# Analog_Input.net
KiCad netlist of a schematic drawn in Altium Designer
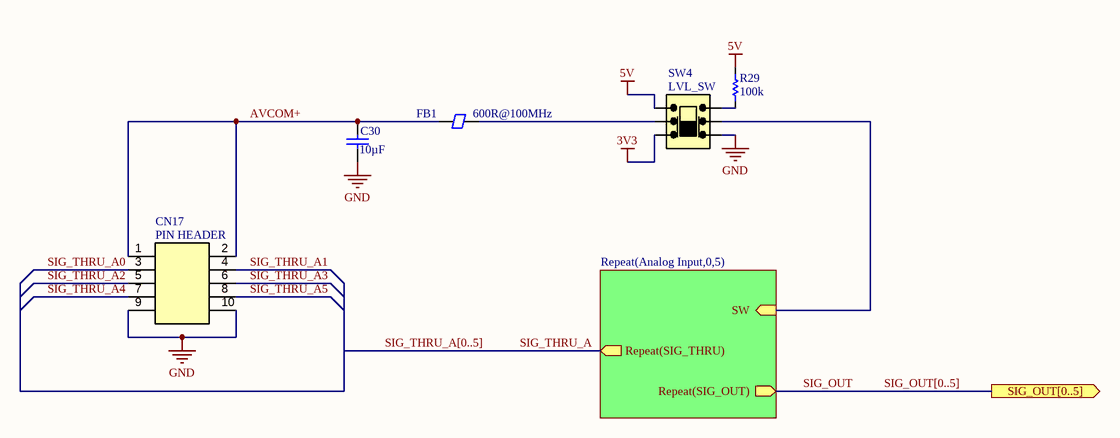
[diagram p0: Analog Input.SchDoc]

(export (version "E")
  (design (tool "Eeschema 10.0.6"))
  (components
    (comp (ref "C30")
      (value "10µF")
      (footprint "CAP_CHIP_0603")
      (fields
        (field (name "PARTNUMBER") "GRM188R6YA106MA73D")
        (field (name "TOLERANCE") "20%")
        (field (name "Comment") "C0603-10uF-35V")
      )
      (libsource (lib "Sainsbury Wellcome Centre") (part "Cap"))
    )
    (comp (ref "CN17")
      (value "PIN HEADER")
      (footprint "PIN_2.54_2X5P")
      (fields (field (name "PARTNUMBER") "PZ254V-12-10P"))
      (libsource (lib "Sainsbury Wellcome Centre") (part "Header_2X5P"))
    )
    (comp (ref "FB1")
      (value "600R@100MHz")
      (footprint "FB_CHIP_0603")
      (description "Ferrite Chip, 1 Function(s), 0.2A, 2 Pin(s)")
      (fields (field (name "PARTNUMBER") "GZ1608D601TF") (field (name "Comment") "FB0603-600R-0.2A"))
      (libsource (lib "Sainsbury Wellcome Centre") (part "Bead"))
    )
    (comp (ref "R29")
      (value "100k")
      (footprint "RES_CHIP_0603")
      (description "100mW Thick Film Resistors 75V ±100ppm/℃ ±1% 0603 Chip Resistor")
      (fields (field (name "PARTNUMBER") "0603WAF1003T5E") (field (name "TOLERANCE") "1%"))
      (libsource (lib "Sainsbury Wellcome Centre") (part "Res"))
    )
    (comp (ref "SW4")
      (value "LVL_SW")
      (footprint "SW_SLIDE_OS202013MT8")
      (description "Switch Slide ON ON DPDT Top Slide 0.3A 30VDC 10000Cycles PC Pins Thru-Hole Bulk")
      (fields (field (name "PARTNUMBER") "OS202013MT8QN1"))
      (libsource (lib "Sainsbury Wellcome Centre") (part "SLIDE_DPDT"))
    )
  )
  (nets
    (net (code "7") (name "/AVCOM+") (class "Default")
      (node (ref "C30") (pin "2") (pinfunction "2_2") (pintype "passive"))
      (node (ref "CN17") (pin "1") (pinfunction "1_1") (pintype "passive"))
      (node (ref "CN17") (pin "2") (pinfunction "2_2") (pintype "passive"))
      (node (ref "FB1") (pin "2") (pinfunction "2_2") (pintype "passive"))
    )
    (net (code "11") (name "/SIG_THRU_A0") (class "Default")
      (node (ref "CN17") (pin "3") (pinfunction "3_3") (pintype "passive"))
    )
    (net (code "12") (name "/SIG_THRU_A1") (class "Default")
      (node (ref "CN17") (pin "4") (pinfunction "4_4") (pintype "passive"))
    )
    (net (code "13") (name "/SIG_THRU_A2") (class "Default")
      (node (ref "CN17") (pin "5") (pinfunction "5_5") (pintype "passive"))
    )
    (net (code "14") (name "/SIG_THRU_A3") (class "Default")
      (node (ref "CN17") (pin "6") (pinfunction "6_6") (pintype "passive"))
    )
    (net (code "15") (name "/SIG_THRU_A4") (class "Default")
      (node (ref "CN17") (pin "7") (pinfunction "7_7") (pintype "passive"))
    )
    (net (code "16") (name "/SIG_THRU_A5") (class "Default")
      (node (ref "CN17") (pin "8") (pinfunction "8_8") (pintype "passive"))
    )
    (net (code "18") (name "/SW") (class "Default")
      (node (ref "SW4") (pin "2") (pinfunction "COMA_2") (pintype "passive"))
    )
    (net (code "19") (name "3V3") (class "Default")
      (node (ref "SW4") (pin "4") (pinfunction "NCB_4") (pintype "passive"))
    )
    (net (code "20") (name "5V") (class "Default")
      (node (ref "R29") (pin "2") (pinfunction "2_2") (pintype "passive"))
      (node (ref "SW4") (pin "6") (pinfunction "NOB_6") (pintype "passive"))
    )
    (net (code "21") (name "GND") (class "Default")
      (node (ref "C30") (pin "1") (pinfunction "1_1") (pintype "passive"))
      (node (ref "CN17") (pin "10") (pinfunction "10_10") (pintype "passive"))
      (node (ref "CN17") (pin "9") (pinfunction "9_9") (pintype "passive"))
      (node (ref "SW4") (pin "1") (pinfunction "NCA_1") (pintype "passive"))
    )
    (net (code "22") (name "Net-(SW4-COMB)") (class "Default")
      (node (ref "FB1") (pin "1") (pinfunction "1_1") (pintype "passive"))
      (node (ref "SW4") (pin "5") (pinfunction "COMB_5") (pintype "passive"))
    )
    (net (code "23") (name "Net-(SW4-NOA)") (class "Default")
      (node (ref "R29") (pin "1") (pinfunction "1_1") (pintype "passive"))
      (node (ref "SW4") (pin "3") (pinfunction "NOA_3") (pintype "passive"))
    )
  )
)
